# IO_Peripherals.net
KiCad netlist of a schematic drawn in Altium Designer
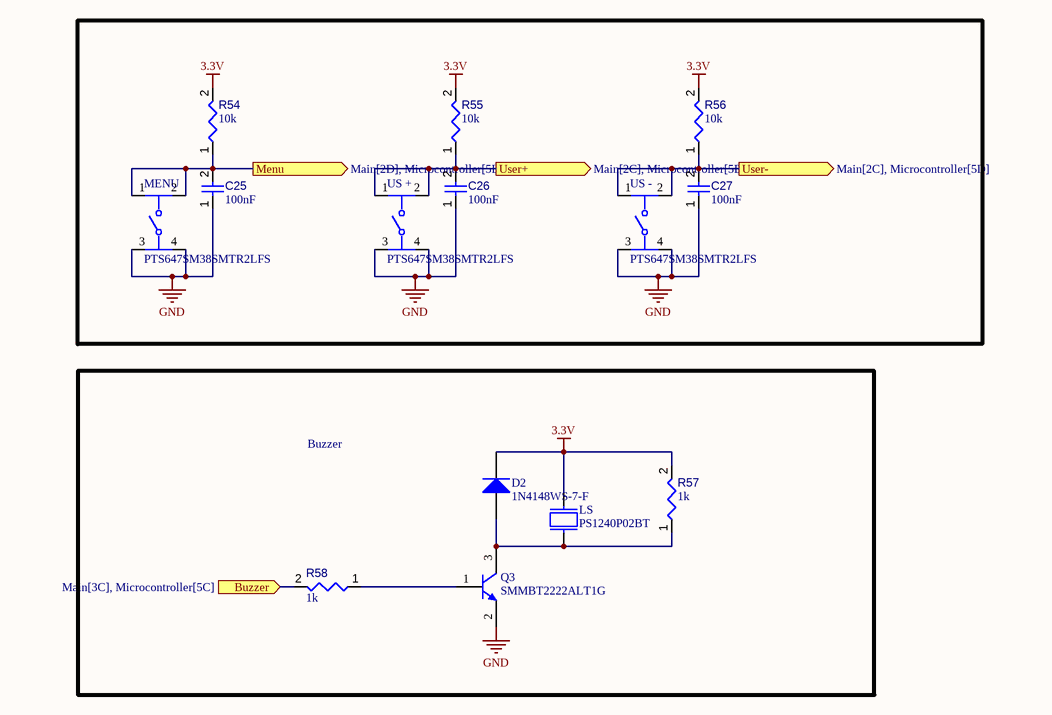
[diagram p0: IO_Peripherals.SchDoc]

(export (version "E")
  (design (tool "Eeschema 10.0.6"))
  (components
    (comp (ref "C25")
      (value "100nF")
      (footprint "CAPC2013X95X50LL10T25")
      (description "Chip Capacitor, 100 nF, +/- 10%, 50 V, 0805 (2012 Metric)")
      (fields (field (name "TOLERANCE") "10%") (field (name "Comment") "Capacitor 100 nF +/-10% 50 V 0805"))
      (libsource (lib "Buddhi Rashmika") (part "CAP-NP-2"))
    )
    (comp (ref "C26")
      (value "100nF")
      (footprint "CAPC2013X95X50LL10T25")
      (description "Chip Capacitor, 100 nF, +/- 10%, 50 V, 0805 (2012 Metric)")
      (fields (field (name "TOLERANCE") "10%") (field (name "Comment") "Capacitor 100 nF +/-10% 50 V 0805"))
      (libsource (lib "Buddhi Rashmika") (part "CAP-NP-2"))
    )
    (comp (ref "C27")
      (value "100nF")
      (footprint "CAPC2013X95X50LL10T25")
      (description "Chip Capacitor, 100 nF, +/- 10%, 50 V, 0805 (2012 Metric)")
      (fields (field (name "TOLERANCE") "10%") (field (name "Comment") "Capacitor 100 nF +/-10% 50 V 0805"))
      (libsource (lib "Buddhi Rashmika") (part "CAP-NP-2"))
    )
    (comp (ref "D2")
      (value "1N4148WS-7-F")
      (footprint "DIOD-SOD323-2-A_V")
      (description "Rectifier Diode Small Signal Switching 75V 0.3A 4ns 2-Pin SOD-323 T/R")
      (libsource (lib "Buddhi Rashmika") (part "D-AK-2"))
    )
    (comp (ref "LS")
      (value "PS1240P02BT")
      (footprint "XDCR_PS1240P02BT")
      (description "Buzzers Transducer, Externally Driven Piezo 3V 4kHz 60dB @ 3V, 10cm Through Hole PC Pins")
      (fields (field (name "MF") "TDK"))
      (libsource (lib "Buddhi Rashmika") (part "PS1240P02BT"))
    )
    (comp (ref "MENU")
      (value "PTS647SM38SMTR2LFS")
      (footprint "FP-PTS647SM38SMTR2LFS-MFG")
      (description "Switch Tactile OFF Mom SPST Round Button Gull Wing 50mA 12VDC 100000Cycles 1.77N Surface Mount T/R")
      (libsource (lib "Buddhi Rashmika") (part "1adf0dd01260c80cf25a44bfd6b99ba"))
    )
    (comp (ref "Q3")
      (value "SMMBT2222ALT1G")
      (footprint "ONSC-SOT-23-3-318-08_V")
      (description "General Purpose Transistor, NPN Silicon, 3-Pin SOT-23, Pb-Free, Tape and Reel")
      (fields (field (name "MANUFACTURER") "On Semiconductor"))
      (libsource (lib "Altium Content Vault") (part "ONSC-NPN-B1E2C3-3"))
    )
    (comp (ref "R54")
      (value "10k")
      (footprint "RESC2013X50X35ML15T15")
      (description "Chip Resistor, 10 KOhm, +/- 1%, 125 mW, -55 to 155 degC, 0805 (2012 Metric)")
      (fields (field (name "TOLERANCE") "1%") (field (name "POWER") "125mW"))
      (libsource (lib "Buddhi Rashmika") (part "RES-2"))
    )
    (comp (ref "R55")
      (value "10k")
      (footprint "RESC2013X50X35ML15T15")
      (description "Chip Resistor, 10 KOhm, +/- 1%, 125 mW, -55 to 155 degC, 0805 (2012 Metric)")
      (fields (field (name "TOLERANCE") "1%") (field (name "POWER") "125mW"))
      (libsource (lib "Buddhi Rashmika") (part "RES-2"))
    )
    (comp (ref "R56")
      (value "10k")
      (footprint "RESC2013X50X35ML15T15")
      (description "Chip Resistor, 10 KOhm, +/- 1%, 125 mW, -55 to 155 degC, 0805 (2012 Metric)")
      (fields (field (name "TOLERANCE") "1%") (field (name "POWER") "125mW"))
      (libsource (lib "Buddhi Rashmika") (part "RES-2"))
    )
    (comp (ref "R57")
      (value "1k")
      (footprint "RESC0805(2012)_L")
      (description "Chip Resistor, 1 kOhms, +/-5%, 125 mW, -55 to 155 degC, 0805")
      (fields (field (name "TOLERANCE") "5%") (field (name "POWER") "125mW"))
      (libsource (lib "Buddhi Rashmika") (part "RES-2"))
    )
    (comp (ref "R58")
      (value "1k")
      (footprint "RESC0805(2012)_L")
      (description "Chip Resistor, 1 kOhms, +/-5%, 125 mW, -55 to 155 degC, 0805")
      (fields (field (name "TOLERANCE") "5%") (field (name "POWER") "125mW"))
      (libsource (lib "Buddhi Rashmika") (part "RES-2"))
    )
    (comp (ref "US +")
      (value "PTS647SM38SMTR2LFS")
      (footprint "FP-PTS647SM38SMTR2LFS-MFG")
      (description "Switch Tactile OFF Mom SPST Round Button Gull Wing 50mA 12VDC 100000Cycles 1.77N Surface Mount T/R")
      (libsource (lib "Buddhi Rashmika") (part "1adf0dd01260c80cf25a44bfd6b99ba"))
    )
    (comp (ref "US -")
      (value "PTS647SM38SMTR2LFS")
      (footprint "FP-PTS647SM38SMTR2LFS-MFG")
      (description "Switch Tactile OFF Mom SPST Round Button Gull Wing 50mA 12VDC 100000Cycles 1.77N Surface Mount T/R")
      (libsource (lib "Buddhi Rashmika") (part "1adf0dd01260c80cf25a44bfd6b99ba"))
    )
  )
  (nets
    (net (code "1") (name "/Buzzer") (class "Default")
      (node (ref "R58") (pin "2") (pinfunction "2_2") (pintype "passive"))
    )
    (net (code "2") (name "/Menu") (class "Default")
      (node (ref "C25") (pin "2") (pinfunction "2_2") (pintype "passive"))
      (node (ref "MENU") (pin "1") (pinfunction "1_1") (pintype "passive"))
      (node (ref "MENU") (pin "2") (pinfunction "2_2") (pintype "passive"))
      (node (ref "R54") (pin "1") (pinfunction "1_1") (pintype "passive"))
    )
    (net (code "3") (name "/User+") (class "Default")
      (node (ref "C26") (pin "2") (pinfunction "2_2") (pintype "passive"))
      (node (ref "R55") (pin "1") (pinfunction "1_1") (pintype "passive"))
      (node (ref "US +") (pin "1") (pinfunction "1_1") (pintype "passive"))
      (node (ref "US +") (pin "2") (pinfunction "2_2") (pintype "passive"))
    )
    (net (code "4") (name "/User-") (class "Default")
      (node (ref "C27") (pin "2") (pinfunction "2_2") (pintype "passive"))
      (node (ref "R56") (pin "1") (pinfunction "1_1") (pintype "passive"))
      (node (ref "US -") (pin "1") (pinfunction "1_1") (pintype "passive"))
      (node (ref "US -") (pin "2") (pinfunction "2_2") (pintype "passive"))
    )
    (net (code "5") (name "3.3V") (class "Default")
      (node (ref "D2") (pin "2") (pinfunction "K_2") (pintype "passive"))
      (node (ref "LS") (pin "2") (pinfunction "2_2") (pintype "passive"))
      (node (ref "R54") (pin "2") (pinfunction "2_2") (pintype "passive"))
      (node (ref "R55") (pin "2") (pinfunction "2_2") (pintype "passive"))
      (node (ref "R56") (pin "2") (pinfunction "2_2") (pintype "passive"))
      (node (ref "R57") (pin "2") (pinfunction "2_2") (pintype "passive"))
    )
    (net (code "6") (name "GND") (class "Default")
      (node (ref "C25") (pin "1") (pinfunction "1_1") (pintype "passive"))
      (node (ref "C26") (pin "1") (pinfunction "1_1") (pintype "passive"))
      (node (ref "C27") (pin "1") (pinfunction "1_1") (pintype "passive"))
      (node (ref "MENU") (pin "3") (pinfunction "3_3") (pintype "passive"))
      (node (ref "MENU") (pin "4") (pinfunction "4_4") (pintype "passive"))
      (node (ref "Q3") (pin "2") (pinfunction "E_2") (pintype "passive"))
      (node (ref "US +") (pin "3") (pinfunction "3_3") (pintype "passive"))
      (node (ref "US +") (pin "4") (pinfunction "4_4") (pintype "passive"))
      (node (ref "US -") (pin "3") (pinfunction "3_3") (pintype "passive"))
      (node (ref "US -") (pin "4") (pinfunction "4_4") (pintype "passive"))
    )
    (net (code "7") (name "Net-(D2-A)") (class "Default")
      (node (ref "D2") (pin "1") (pinfunction "A_1") (pintype "passive"))
      (node (ref "LS") (pin "1") (pinfunction "1_1") (pintype "passive"))
      (node (ref "Q3") (pin "3") (pinfunction "C_3") (pintype "passive"))
      (node (ref "R57") (pin "1") (pinfunction "1_1") (pintype "passive"))
    )
    (net (code "8") (name "Net-(Q3-B)") (class "Default")
      (node (ref "Q3") (pin "1") (pinfunction "B_1") (pintype "passive"))
      (node (ref "R58") (pin "1") (pinfunction "1_1") (pintype "passive"))
    )
  )
)
